# KO_V3.net
KiCad netlist of a schematic drawn in EAGLE
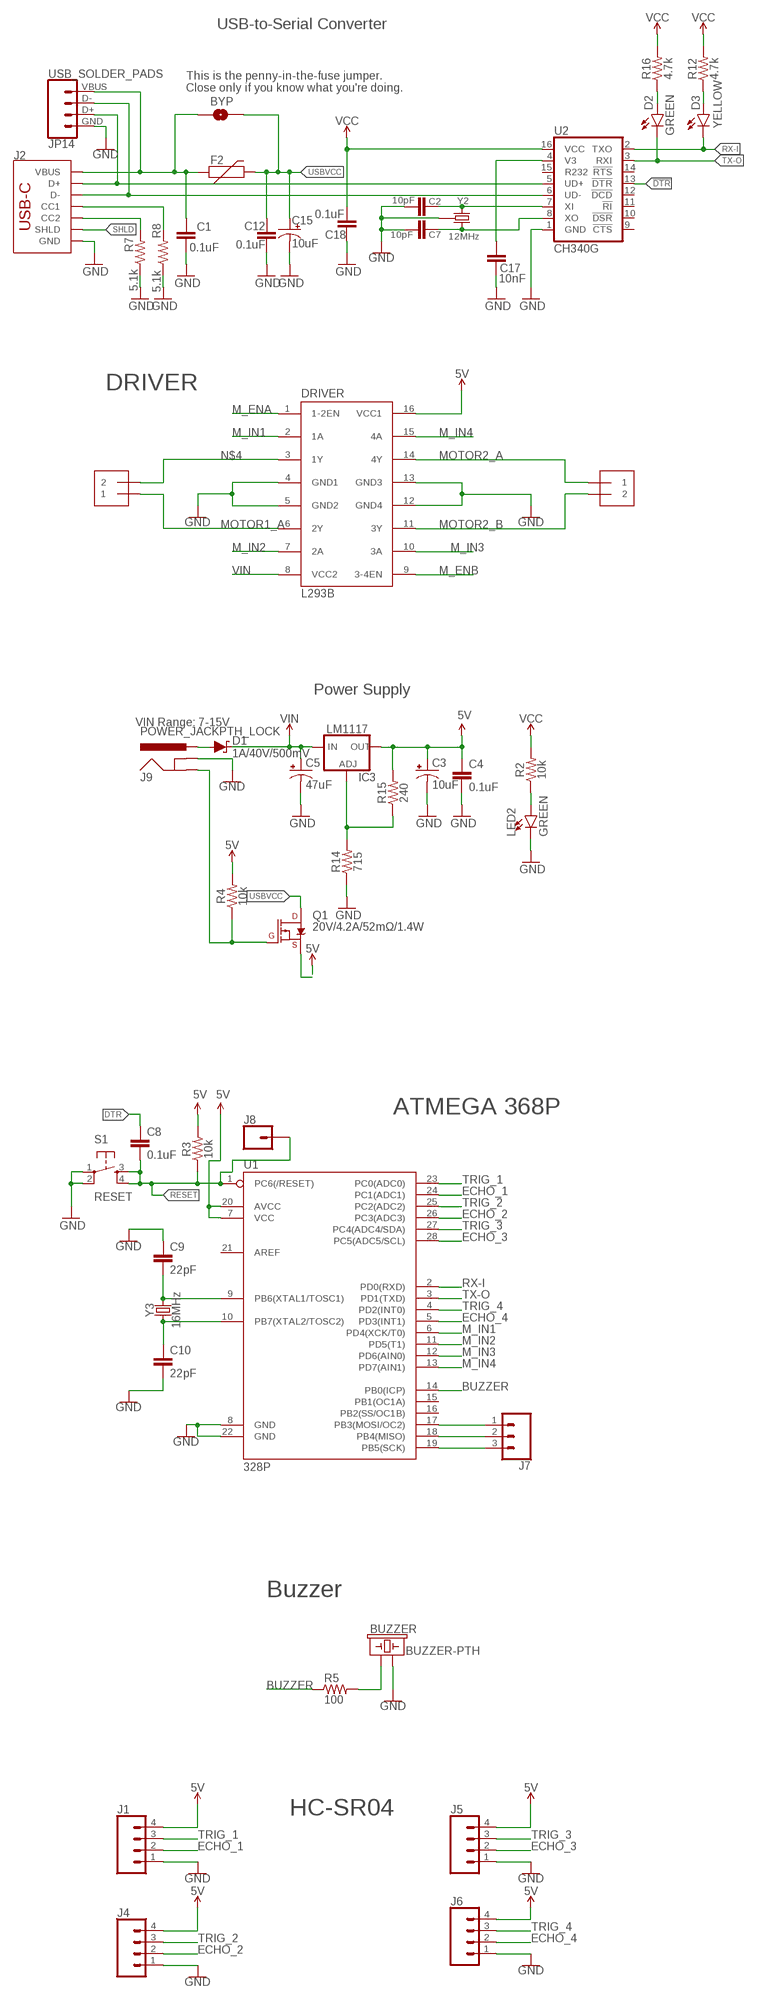
[diagram p0: schematic, sheet 1]

(export (version "E")
  (design (tool "Eeschema 10.0.6"))
  (components
    (comp (ref "BUZZER")
      (value "BUZZER-PTH")
      (footprint "eagle-import:BUZZER-12MM")
      (libsource (lib "eagle-import") (part "BUZZER-PTH"))
    )
    (comp (ref "BYP")
      (value "JUMPER-SMT_2_NO_SILK")
      (footprint "eagle-import:SMT-JUMPER_2_NO_SILK")
      (libsource (lib "eagle-import") (part "JUMPER-SMT_2_NO_SILK"))
    )
    (comp (ref "C1")
      (value "0.1uF")
      (footprint "eagle-import:0603")
      (libsource (lib "eagle-import") (part "0.1UF-0603-25V-(+80/-20%)"))
    )
    (comp (ref "C2")
      (value "10pF")
      (footprint "eagle-import:0603")
      (libsource (lib "eagle-import") (part "10PF-0603-50V-5%"))
    )
    (comp (ref "C3")
      (value "10uF")
      (footprint "eagle-import:EIA3216")
      (libsource (lib "eagle-import") (part "10UF-POLAR-EIA3216-16V-10%(TANT)"))
    )
    (comp (ref "C4")
      (value "0.1uF")
      (footprint "eagle-import:0603")
      (libsource (lib "eagle-import") (part "0.1UF-0603-25V-(+80/-20%)"))
    )
    (comp (ref "C5")
      (value "47uF")
      (footprint "eagle-import:PANASONIC_D")
      (libsource (lib "eagle-import") (part "47UF-POLAR-PANASONIC_D-35V-20%"))
    )
    (comp (ref "C7")
      (value "10pF")
      (footprint "eagle-import:0603")
      (libsource (lib "eagle-import") (part "10PF-0603-50V-5%"))
    )
    (comp (ref "C8")
      (value "0.1uF")
      (footprint "eagle-import:0603")
      (libsource (lib "eagle-import") (part "0.1UF-0603-25V-(+80/-20%)"))
    )
    (comp (ref "C9")
      (value "22pF")
      (footprint "eagle-import:0603")
      (libsource (lib "eagle-import") (part "22PF-0603-50V-5%"))
    )
    (comp (ref "C10")
      (value "22pF")
      (footprint "eagle-import:0603")
      (libsource (lib "eagle-import") (part "22PF-0603-50V-5%"))
    )
    (comp (ref "C12")
      (value "0.1uF")
      (footprint "eagle-import:0603")
      (libsource (lib "eagle-import") (part "0.1UF-0603-25V-(+80/-20%)"))
    )
    (comp (ref "C15")
      (value "10uF")
      (footprint "eagle-import:EIA3216")
      (libsource (lib "eagle-import") (part "10UF-POLAR-EIA3216-16V-10%(TANT)"))
    )
    (comp (ref "C17")
      (value "10nF")
      (footprint "eagle-import:0603")
      (libsource (lib "eagle-import") (part "10NF-0603-50V-10%"))
    )
    (comp (ref "C18")
      (value "0.1uF")
      (footprint "eagle-import:0603")
      (libsource (lib "eagle-import") (part "0.1UF-0603-25V-(+80/-20%)"))
    )
    (comp (ref "D1")
      (value "1A/40V/500mV")
      (footprint "eagle-import:SMA-DIODE")
      (libsource (lib "eagle-import") (part "DIODE-SCHOTTKY-SS14"))
    )
    (comp (ref "D2")
      (value "GREEN")
      (footprint "eagle-import:LED-1206")
      (libsource (lib "eagle-import") (part "LED-GREENLILYPAD"))
    )
    (comp (ref "D3")
      (value "YELLOW")
      (footprint "eagle-import:LED-1206-HIDDENSILK")
      (libsource (lib "eagle-import") (part "LED-YELLOW_HIDDENSILK"))
    )
    (comp (ref "DRIVER")
      (value "L293B")
      (footprint "eagle-import:DIL16")
      (fields (field (name "MPN") "L293D"))
      (libsource (lib "eagle-import") (part "L293D"))
    )
    (comp (ref "F2")
      (value "6V/2A")
      (footprint "eagle-import:1210")
      (libsource (lib "eagle-import") (part "PPTC_6V2A"))
    )
    (comp (ref "IC3")
      (value "LM1117")
      (footprint "eagle-import:SOT223")
      (fields (field (name "PROD_ID") "VREG-08170"))
      (libsource (lib "eagle-import") (part "V_REG_LM1117SOT223"))
    )
    (comp (ref "J1")
      (value "CONN_04")
      (footprint "eagle-import:1X04")
      (libsource (lib "eagle-import") (part "CONN_04"))
    )
    (comp (ref "J2")
      (value "USB Female Type C Connector")
      (footprint "eagle-import:USB-C-16P-2LAYER-PADS")
      (libsource (lib "eagle-import") (part "USB_C_2-LAYER_PADS"))
    )
    (comp (ref "J4")
      (value "CONN_04")
      (footprint "eagle-import:1X04")
      (libsource (lib "eagle-import") (part "CONN_04"))
    )
    (comp (ref "J5")
      (value "CONN_04")
      (footprint "eagle-import:1X04")
      (libsource (lib "eagle-import") (part "CONN_04"))
    )
    (comp (ref "J6")
      (value "CONN_04")
      (footprint "eagle-import:1X04")
      (libsource (lib "eagle-import") (part "CONN_04"))
    )
    (comp (ref "J7")
      (value "CONN_03LONGPADS")
      (footprint "eagle-import:1X03_LONGPADS")
      (libsource (lib "eagle-import") (part "CONN_03LONGPADS"))
    )
    (comp (ref "J8")
      (value "CONN_01OFFSET")
      (footprint "eagle-import:1X01_OFFSET")
      (libsource (lib "eagle-import") (part "CONN_01OFFSET"))
    )
    (comp (ref "J9")
      (value "POWER_JACKPTH_LOCK")
      (footprint "eagle-import:POWER_JACK_PTH_LOCK")
      (libsource (lib "eagle-import") (part "POWER_JACKPTH_LOCK"))
    )
    (comp (ref "JP14")
      (value "USB_SOLDER_PADS")
      (footprint "eagle-import:USB-SOLDER-PADS")
      (libsource (lib "eagle-import") (part "USB_SOLDER_PADS"))
    )
    (comp (ref "LED2")
      (value "GREEN")
      (footprint "eagle-import:LED-1206")
      (libsource (lib "eagle-import") (part "LED-GREENLILYPAD"))
    )
    (comp (ref "MOTOR_1")
      (value "1X2-3.5MM")
      (footprint "eagle-import:1X2-3.5MM")
      (libsource (lib "eagle-import") (part "1X2-3.5MM"))
    )
    (comp (ref "MOTOR_2")
      (value "1X2-3.5MM")
      (footprint "eagle-import:1X2-3.5MM")
      (libsource (lib "eagle-import") (part "1X2-3.5MM"))
    )
    (comp (ref "Q1")
      (value "20V/4.2A/52mΩ/1.4W")
      (footprint "eagle-import:SOT23-3")
      (libsource (lib "eagle-import") (part "MOSFET_PCH-DMG2305UX-7"))
    )
    (comp (ref "R2")
      (value "10k")
      (footprint "eagle-import:0603")
      (libsource (lib "eagle-import") (part "10KOHM-0603-1/10W-1%"))
    )
    (comp (ref "R3")
      (value "10k")
      (footprint "eagle-import:0603")
      (libsource (lib "eagle-import") (part "10KOHM-0603-1/10W-1%"))
    )
    (comp (ref "R4")
      (value "10k")
      (footprint "eagle-import:0603")
      (libsource (lib "eagle-import") (part "10KOHM-0603-1/10W-1%"))
    )
    (comp (ref "R5")
      (value "100")
      (footprint "eagle-import:RC-MASTER-SMD_R1206MP")
      (libsource (lib "eagle-import") (part "RC-MASTER-SMD_R_1206MP"))
    )
    (comp (ref "R7")
      (value "5.1k")
      (footprint "eagle-import:0603")
      (libsource (lib "eagle-import") (part "5.1KOHM5.1KOHM-0603-1/10W-1%"))
    )
    (comp (ref "R8")
      (value "5.1k")
      (footprint "eagle-import:0603")
      (libsource (lib "eagle-import") (part "5.1KOHM5.1KOHM-0603-1/10W-1%"))
    )
    (comp (ref "R12")
      (value "4.7k")
      (footprint "eagle-import:0603")
      (libsource (lib "eagle-import") (part "4.7KOHM-0603-1/10W-1%"))
    )
    (comp (ref "R14")
      (value "715")
      (footprint "eagle-import:0603")
      (libsource (lib "eagle-import") (part "715OHM-0603-1/10W-1%"))
    )
    (comp (ref "R15")
      (value "240")
      (footprint "eagle-import:0603")
      (libsource (lib "eagle-import") (part "240OHM-0603-1/10W-1%"))
    )
    (comp (ref "R16")
      (value "4.7k")
      (footprint "eagle-import:0603")
      (libsource (lib "eagle-import") (part "4.7KOHM-0603-1/10W-1%"))
    )
    (comp (ref "S1")
      (value "RESET")
      (footprint "eagle-import:TACTILE-SWITCH-SMD")
      (libsource (lib "eagle-import") (part "SWITCH_SPST_4_PINSQUARE"))
    )
    (comp (ref "U1")
      (value "328P")
      (footprint "eagle-import:DIP28")
      (libsource (lib "eagle-import") (part "ATMEGA328P_PDIP"))
    )
    (comp (ref "U2")
      (value "CH340G")
      (footprint "eagle-import:SO016")
      (libsource (lib "eagle-import") (part "CH340GSMD"))
    )
    (comp (ref "Y2")
      (value "12MHz")
      (footprint "eagle-import:CRYSTAL-SMD-3.2X2.5MM")
      (libsource (lib "eagle-import") (part "CRYSTAL-GROUNDEDSMD-3.2X2.5"))
    )
    (comp (ref "Y3")
      (value "16MHz")
      (footprint "eagle-import:HC49US")
      (libsource (lib "eagle-import") (part "CRYSTAL-16MHZPTH-HC49US"))
    )
  )
  (nets
    (net (code "1") (name "/BUZZER") (class "Default")
      (node (ref "R5") (pin "1") (pinfunction "1_1") (pintype "passive"))
      (node (ref "U1") (pin "14") (pinfunction "PB0(ICP)_14") (pintype "bidirectional"))
    )
    (net (code "2") (name "/ECHO_1") (class "Default")
      (node (ref "J1") (pin "2") (pinfunction "2_2") (pintype "passive"))
      (node (ref "U1") (pin "24") (pinfunction "PC1(ADC1)_24") (pintype "bidirectional"))
    )
    (net (code "3") (name "/ECHO_2") (class "Default")
      (node (ref "J4") (pin "2") (pinfunction "2_2") (pintype "passive"))
      (node (ref "U1") (pin "26") (pinfunction "PC3(ADC3)_26") (pintype "bidirectional"))
    )
    (net (code "4") (name "/ECHO_3") (class "Default")
      (node (ref "J5") (pin "2") (pinfunction "2_2") (pintype "passive"))
      (node (ref "U1") (pin "28") (pinfunction "PC5(ADC5/SCL)_28") (pintype "bidirectional"))
    )
    (net (code "5") (name "/ECHO_4") (class "Default")
      (node (ref "J6") (pin "2") (pinfunction "2_2") (pintype "passive"))
      (node (ref "U1") (pin "5") (pinfunction "PD3(INT1)_5") (pintype "bidirectional"))
    )
    (net (code "6") (name "/MOTOR1_A") (class "Default")
      (node (ref "DRIVER") (pin "6") (pinfunction "2Y_6") (pintype "output"))
      (node (ref "MOTOR_2") (pin "1") (pinfunction "1_1") (pintype "passive"))
    )
    (net (code "7") (name "/MOTOR2_A") (class "Default")
      (node (ref "DRIVER") (pin "14") (pinfunction "4Y_14") (pintype "output"))
      (node (ref "MOTOR_1") (pin "1") (pinfunction "1_1") (pintype "passive"))
    )
    (net (code "8") (name "/MOTOR2_B") (class "Default")
      (node (ref "DRIVER") (pin "11") (pinfunction "3Y_11") (pintype "output"))
      (node (ref "MOTOR_1") (pin "2") (pinfunction "2_2") (pintype "passive"))
    )
    (net (code "9") (name "/M_ENA") (class "Default")
      (node (ref "DRIVER") (pin "1") (pinfunction "1-2EN_1") (pintype "input"))
    )
    (net (code "10") (name "/M_ENB") (class "Default")
      (node (ref "DRIVER") (pin "9") (pinfunction "3-4EN_9") (pintype "input"))
    )
    (net (code "11") (name "/M_IN1") (class "Default")
      (node (ref "DRIVER") (pin "2") (pinfunction "1A_2") (pintype "input"))
      (node (ref "U1") (pin "6") (pinfunction "PD4(XCK/T0)_6") (pintype "bidirectional"))
    )
    (net (code "12") (name "/M_IN2") (class "Default")
      (node (ref "DRIVER") (pin "7") (pinfunction "2A_7") (pintype "input"))
      (node (ref "U1") (pin "11") (pinfunction "PD5(T1)_11") (pintype "bidirectional"))
    )
    (net (code "13") (name "/M_IN3") (class "Default")
      (node (ref "DRIVER") (pin "10") (pinfunction "3A_10") (pintype "input"))
      (node (ref "U1") (pin "12") (pinfunction "PD6(AIN0)_12") (pintype "bidirectional"))
    )
    (net (code "14") (name "/M_IN4") (class "Default")
      (node (ref "DRIVER") (pin "15") (pinfunction "4A_15") (pintype "input"))
      (node (ref "U1") (pin "13") (pinfunction "PD7(AIN1)_13") (pintype "bidirectional"))
    )
    (net (code "15") (name "/N$4") (class "Default")
      (node (ref "DRIVER") (pin "3") (pinfunction "1Y_3") (pintype "output"))
      (node (ref "MOTOR_2") (pin "2") (pinfunction "2_2") (pintype "passive"))
    )
    (net (code "16") (name "/TRIG_1") (class "Default")
      (node (ref "J1") (pin "3") (pinfunction "3_3") (pintype "passive"))
      (node (ref "U1") (pin "23") (pinfunction "PC0(ADC0)_23") (pintype "bidirectional"))
    )
    (net (code "17") (name "/TRIG_2") (class "Default")
      (node (ref "J4") (pin "3") (pinfunction "3_3") (pintype "passive"))
      (node (ref "U1") (pin "25") (pinfunction "PC2(ADC2)_25") (pintype "bidirectional"))
    )
    (net (code "18") (name "/TRIG_3") (class "Default")
      (node (ref "J5") (pin "3") (pinfunction "3_3") (pintype "passive"))
      (node (ref "U1") (pin "27") (pinfunction "PC4(ADC4/SDA)_27") (pintype "bidirectional"))
    )
    (net (code "19") (name "/TRIG_4") (class "Default")
      (node (ref "J6") (pin "3") (pinfunction "3_3") (pintype "passive"))
      (node (ref "U1") (pin "4") (pinfunction "PD2(INT0)_4") (pintype "bidirectional"))
    )
    (net (code "20") (name "/~{DTR}") (class "Default")
      (node (ref "U2") (pin "13") (pinfunction "~{DTR}_13") (pintype "bidirectional"))
    )
    (net (code "21") (name "5V") (class "Default")
      (node (ref "C3") (pin "+") (pinfunction "+_+") (pintype "passive"))
      (node (ref "C4") (pin "1") (pinfunction "1_1") (pintype "passive"))
      (node (ref "DRIVER") (pin "16") (pinfunction "VCC1_16") (pintype "power_in"))
      (node (ref "IC3") (pin "2") (pinfunction "OUT_2") (pintype "output"))
      (node (ref "IC3") (pin "4") (pinfunction "OUT_4") (pintype "output"))
      (node (ref "J1") (pin "4") (pinfunction "4_4") (pintype "passive"))
      (node (ref "J4") (pin "4") (pinfunction "4_4") (pintype "passive"))
      (node (ref "J5") (pin "4") (pinfunction "4_4") (pintype "passive"))
      (node (ref "J6") (pin "4") (pinfunction "4_4") (pintype "passive"))
      (node (ref "Q1") (pin "2") (pinfunction "S_2") (pintype "bidirectional"))
      (node (ref "R15") (pin "2") (pinfunction "2_2") (pintype "passive"))
      (node (ref "R3") (pin "2") (pinfunction "2_2") (pintype "passive"))
      (node (ref "R4") (pin "2") (pinfunction "2_2") (pintype "passive"))
      (node (ref "U1") (pin "20") (pinfunction "AVCC_20") (pintype "bidirectional"))
      (node (ref "U1") (pin "7") (pinfunction "VCC_7") (pintype "bidirectional"))
    )
    (net (code "22") (name "DTR") (class "Default")
      (node (ref "C8") (pin "1") (pinfunction "1_1") (pintype "passive"))
    )
    (net (code "23") (name "GND") (class "Default")
      (node (ref "BUZZER") (pin "-") (pinfunction "2_-") (pintype "passive"))
      (node (ref "C1") (pin "2") (pinfunction "2_2") (pintype "passive"))
      (node (ref "C10") (pin "2") (pinfunction "2_2") (pintype "passive"))
      (node (ref "C12") (pin "2") (pinfunction "2_2") (pintype "passive"))
      (node (ref "C15") (pin "-") (pinfunction "-_-") (pintype "passive"))
      (node (ref "C17") (pin "2") (pinfunction "2_2") (pintype "passive"))
      (node (ref "C18") (pin "2") (pinfunction "2_2") (pintype "passive"))
      (node (ref "C2") (pin "2") (pinfunction "2_2") (pintype "passive"))
      (node (ref "C3") (pin "-") (pinfunction "-_-") (pintype "passive"))
      (node (ref "C4") (pin "2") (pinfunction "2_2") (pintype "passive"))
      (node (ref "C5") (pin "-") (pinfunction "-_-") (pintype "passive"))
      (node (ref "C7") (pin "2") (pinfunction "2_2") (pintype "passive"))
      (node (ref "C9") (pin "1") (pinfunction "1_1") (pintype "passive"))
      (node (ref "DRIVER") (pin "12") (pinfunction "GND4_12") (pintype "power_in"))
      (node (ref "DRIVER") (pin "13") (pinfunction "GND3_13") (pintype "power_in"))
      (node (ref "DRIVER") (pin "4") (pinfunction "GND1_4") (pintype "power_in"))
      (node (ref "DRIVER") (pin "5") (pinfunction "GND2_5") (pintype "power_in"))
      (node (ref "J1") (pin "1") (pinfunction "1_1") (pintype "passive"))
      (node (ref "J2") (pin "GND") (pinfunction "GND_GND") (pintype "bidirectional"))
      (node (ref "J2") (pin "GND2") (pinfunction "GND_GND2") (pintype "bidirectional"))
      (node (ref "J4") (pin "1") (pinfunction "1_1") (pintype "passive"))
      (node (ref "J5") (pin "1") (pinfunction "1_1") (pintype "passive"))
      (node (ref "J6") (pin "1") (pinfunction "1_1") (pintype "passive"))
      (node (ref "J9") (pin "GNDBREAK") (pinfunction "GNDBREAK_GNDBREAK") (pintype "bidirectional"))
      (node (ref "JP14") (pin "GND") (pinfunction "4_GND") (pintype "passive"))
      (node (ref "LED2") (pin "C") (pinfunction "C_C") (pintype "passive"))
      (node (ref "R14") (pin "1") (pinfunction "1_1") (pintype "passive"))
      (node (ref "R7") (pin "1") (pinfunction "1_1") (pintype "passive"))
      (node (ref "R8") (pin "1") (pinfunction "1_1") (pintype "passive"))
      (node (ref "S1") (pin "1") (pinfunction "1_1") (pintype "passive"))
      (node (ref "S1") (pin "2") (pinfunction "2_2") (pintype "passive"))
      (node (ref "U1") (pin "22") (pinfunction "GND_22") (pintype "bidirectional"))
      (node (ref "U1") (pin "8") (pinfunction "GND_8") (pintype "bidirectional"))
      (node (ref "U2") (pin "1") (pinfunction "GND_1") (pintype "bidirectional"))
      (node (ref "Y2") (pin "2") (pinfunction "GND_2") (pintype "power_in"))
      (node (ref "Y2") (pin "4") (pinfunction "GND_4") (pintype "power_in"))
    )
    (net (code "24") (name "Net-(BUZZER-1)") (class "Default")
      (node (ref "BUZZER") (pin "+") (pinfunction "1_+") (pintype "passive"))
      (node (ref "R5") (pin "2") (pinfunction "2_2") (pintype "passive"))
    )
    (net (code "25") (name "Net-(D1-PadA)") (class "Default")
      (node (ref "D1") (pin "A") (pinfunction "A_A") (pintype "passive"))
      (node (ref "J9") (pin "PWR") (pinfunction "PWR_PWR") (pintype "bidirectional"))
    )
    (net (code "26") (name "Net-(D2-PadA)") (class "Default")
      (node (ref "D2") (pin "A") (pinfunction "A_A") (pintype "passive"))
      (node (ref "R16") (pin "1") (pinfunction "1_1") (pintype "passive"))
    )
    (net (code "27") (name "Net-(D3-PadA)") (class "Default")
      (node (ref "D3") (pin "A") (pinfunction "A_A") (pintype "passive"))
      (node (ref "R12") (pin "1") (pinfunction "1_1") (pintype "passive"))
    )
    (net (code "28") (name "Net-(IC3-ADJ)") (class "Default")
      (node (ref "IC3") (pin "1") (pinfunction "ADJ_1") (pintype "input"))
      (node (ref "R14") (pin "2") (pinfunction "2_2") (pintype "passive"))
      (node (ref "R15") (pin "1") (pinfunction "1_1") (pintype "passive"))
    )
    (net (code "29") (name "Net-(J2-CC1)") (class "Default")
      (node (ref "J2") (pin "A5") (pinfunction "CC1_A5") (pintype "bidirectional"))
      (node (ref "R8") (pin "2") (pinfunction "2_2") (pintype "passive"))
    )
    (net (code "30") (name "Net-(J2-CC2)") (class "Default")
      (node (ref "J2") (pin "B5") (pinfunction "CC2_B5") (pintype "bidirectional"))
      (node (ref "R7") (pin "2") (pinfunction "2_2") (pintype "passive"))
    )
    (net (code "31") (name "Net-(JP14-1)") (class "Default")
      (node (ref "BYP") (pin "1") (pinfunction "1_1") (pintype "passive"))
      (node (ref "C1") (pin "1") (pinfunction "1_1") (pintype "passive"))
      (node (ref "F2") (pin "1") (pinfunction "1_1") (pintype "bidirectional"))
      (node (ref "J2") (pin "VBUS1") (pinfunction "VBUS_VBUS1") (pintype "bidirectional"))
      (node (ref "J2") (pin "VBUS2") (pinfunction "VBUS_VBUS2") (pintype "bidirectional"))
      (node (ref "JP14") (pin "VBUS") (pinfunction "1_VBUS") (pintype "passive"))
    )
    (net (code "32") (name "Net-(JP14-2)") (class "Default")
      (node (ref "J2") (pin "A7") (pinfunction "D-_A7") (pintype "bidirectional"))
      (node (ref "J2") (pin "B7") (pinfunction "D-_B7") (pintype "bidirectional"))
      (node (ref "JP14") (pin "D-") (pinfunction "2_D-") (pintype "passive"))
      (node (ref "U2") (pin "6") (pinfunction "UD-_6") (pintype "bidirectional"))
    )
    (net (code "33") (name "Net-(JP14-3)") (class "Default")
      (node (ref "J2") (pin "A6") (pinfunction "D+_A6") (pintype "bidirectional"))
      (node (ref "J2") (pin "B6") (pinfunction "D+_B6") (pintype "bidirectional"))
      (node (ref "JP14") (pin "D+") (pinfunction "3_D+") (pintype "passive"))
      (node (ref "U2") (pin "5") (pinfunction "UD+_5") (pintype "bidirectional"))
    )
    (net (code "34") (name "Net-(LED2-PadA)") (class "Default")
      (node (ref "LED2") (pin "A") (pinfunction "A_A") (pintype "passive"))
      (node (ref "R2") (pin "1") (pinfunction "1_1") (pintype "passive"))
    )
    (net (code "35") (name "Net-(Q1-G)") (class "Default")
      (node (ref "J9") (pin "GND") (pinfunction "GND_GND") (pintype "bidirectional"))
      (node (ref "Q1") (pin "1") (pinfunction "G_1") (pintype "bidirectional"))
      (node (ref "R4") (pin "1") (pinfunction "1_1") (pintype "passive"))
    )
    (net (code "36") (name "Net-(U1-PB3(MOSI{slash}OC2))") (class "Default")
      (node (ref "J7") (pin "1") (pinfunction "1_1") (pintype "passive"))
      (node (ref "U1") (pin "17") (pinfunction "PB3(MOSI/OC2)_17") (pintype "bidirectional"))
    )
    (net (code "37") (name "Net-(U1-PB4(MISO))") (class "Default")
      (node (ref "J7") (pin "2") (pinfunction "2_2") (pintype "passive"))
      (node (ref "U1") (pin "18") (pinfunction "PB4(MISO)_18") (pintype "bidirectional"))
    )
    (net (code "38") (name "Net-(U1-PB5(SCK))") (class "Default")
      (node (ref "J7") (pin "3") (pinfunction "3_3") (pintype "passive"))
      (node (ref "U1") (pin "19") (pinfunction "PB5(SCK)_19") (pintype "bidirectional"))
    )
    (net (code "39") (name "Net-(U1-PB6(XTAL1{slash}TOSC1))") (class "Default")
      (node (ref "C9") (pin "2") (pinfunction "2_2") (pintype "passive"))
      (node (ref "U1") (pin "9") (pinfunction "PB6(XTAL1/TOSC1)_9") (pintype "bidirectional"))
      (node (ref "Y3") (pin "2") (pinfunction "2_2") (pintype "passive"))
    )
    (net (code "40") (name "Net-(U1-PB7(XTAL2{slash}TOSC2))") (class "Default")
      (node (ref "C10") (pin "1") (pinfunction "1_1") (pintype "passive"))
      (node (ref "U1") (pin "10") (pinfunction "PB7(XTAL2/TOSC2)_10") (pintype "bidirectional"))
      (node (ref "Y3") (pin "1") (pinfunction "1_1") (pintype "passive"))
    )
    (net (code "41") (name "Net-(U2-V3)") (class "Default")
      (node (ref "C17") (pin "1") (pinfunction "1_1") (pintype "passive"))
      (node (ref "U2") (pin "4") (pinfunction "V3_4") (pintype "bidirectional"))
    )
    (net (code "42") (name "Net-(U2-XI)") (class "Default")
      (node (ref "C2") (pin "1") (pinfunction "1_1") (pintype "passive"))
      (node (ref "U2") (pin "7") (pinfunction "XI_7") (pintype "bidirectional"))
      (node (ref "Y2") (pin "1") (pinfunction "1_1") (pintype "passive"))
    )
    (net (code "43") (name "Net-(U2-XO)") (class "Default")
      (node (ref "C7") (pin "1") (pinfunction "1_1") (pintype "passive"))
      (node (ref "U2") (pin "8") (pinfunction "XO_8") (pintype "bidirectional"))
      (node (ref "Y2") (pin "3") (pinfunction "2_3") (pintype "passive"))
    )
    (net (code "44") (name "RESET") (class "Default")
      (node (ref "C8") (pin "2") (pinfunction "2_2") (pintype "passive"))
      (node (ref "J8") (pin "1") (pinfunction "1_1") (pintype "passive"))
      (node (ref "R3") (pin "1") (pinfunction "1_1") (pintype "passive"))
      (node (ref "S1") (pin "3") (pinfunction "3_3") (pintype "passive"))
      (node (ref "S1") (pin "4") (pinfunction "4_4") (pintype "passive"))
      (node (ref "U1") (pin "1") (pinfunction "PC6(/RESET)_1") (pintype "bidirectional"))
    )
    (net (code "45") (name "RX-I") (class "Default")
      (node (ref "D3") (pin "C") (pinfunction "C_C") (pintype "passive"))
      (node (ref "U1") (pin "2") (pinfunction "PD0(RXD)_2") (pintype "bidirectional"))
      (node (ref "U2") (pin "2") (pinfunction "TXO_2") (pintype "bidirectional"))
    )
    (net (code "46") (name "SHLD") (class "Default")
      (node (ref "J2") (pin "SHLD1") (pinfunction "SHLD_SHLD1") (pintype "bidirectional"))
      (node (ref "J2") (pin "SHLD2") (pinfunction "SHLD_SHLD2") (pintype "bidirectional"))
      (node (ref "J2") (pin "SHLD3") (pinfunction "SHLD_SHLD3") (pintype "bidirectional"))
      (node (ref "J2") (pin "SHLD4") (pinfunction "SHLD_SHLD4") (pintype "bidirectional"))
    )
    (net (code "47") (name "TX-O") (class "Default")
      (node (ref "D2") (pin "C") (pinfunction "C_C") (pintype "passive"))
      (node (ref "U1") (pin "3") (pinfunction "PD1(TXD)_3") (pintype "bidirectional"))
      (node (ref "U2") (pin "3") (pinfunction "RXI_3") (pintype "bidirectional"))
    )
    (net (code "48") (name "USBVCC") (class "Default")
      (node (ref "BYP") (pin "2") (pinfunction "2_2") (pintype "passive"))
      (node (ref "C12") (pin "1") (pinfunction "1_1") (pintype "passive"))
      (node (ref "C15") (pin "+") (pinfunction "+_+") (pintype "passive"))
      (node (ref "F2") (pin "2") (pinfunction "2_2") (pintype "bidirectional"))
      (node (ref "Q1") (pin "3") (pinfunction "D_3") (pintype "bidirectional"))
    )
    (net (code "49") (name "VCC") (class "Default")
      (node (ref "C18") (pin "1") (pinfunction "1_1") (pintype "passive"))
      (node (ref "R12") (pin "2") (pinfunction "2_2") (pintype "passive"))
      (node (ref "R16") (pin "2") (pinfunction "2_2") (pintype "passive"))
      (node (ref "R2") (pin "2") (pinfunction "2_2") (pintype "passive"))
      (node (ref "U2") (pin "16") (pinfunction "VCC_16") (pintype "bidirectional"))
    )
    (net (code "50") (name "VIN") (class "Default")
      (node (ref "C5") (pin "+") (pinfunction "+_+") (pintype "passive"))
      (node (ref "D1") (pin "C") (pinfunction "C_C") (pintype "passive"))
      (node (ref "DRIVER") (pin "8") (pinfunction "VCC2_8") (pintype "power_in"))
      (node (ref "IC3") (pin "3") (pinfunction "IN_3") (pintype "input"))
    )
    (net (code "51") (name "unconnected-(U1-AREF-Pad21)") (class "Default")
      (node (ref "U1") (pin "21") (pinfunction "AREF_21") (pintype "bidirectional"))
    )
    (net (code "52") (name "unconnected-(U1-PB1(OC1A)-Pad15)") (class "Default")
      (node (ref "U1") (pin "15") (pinfunction "PB1(OC1A)_15") (pintype "bidirectional"))
    )
    (net (code "53") (name "unconnected-(U1-PB2(SS{slash}OC1B)-Pad16)") (class "Default")
      (node (ref "U1") (pin "16") (pinfunction "PB2(SS/OC1B)_16") (pintype "bidirectional"))
    )
    (net (code "54") (name "unconnected-(U2-R232-Pad15)") (class "Default")
      (node (ref "U2") (pin "15") (pinfunction "R232_15") (pintype "bidirectional"))
    )
    (net (code "55") (name "unconnected-(U2-~{CTS}-Pad9)") (class "Default")
      (node (ref "U2") (pin "9") (pinfunction "~{CTS}_9") (pintype "bidirectional"))
    )
    (net (code "56") (name "unconnected-(U2-~{DCD}-Pad12)") (class "Default")
      (node (ref "U2") (pin "12") (pinfunction "~{DCD}_12") (pintype "bidirectional"))
    )
    (net (code "57") (name "unconnected-(U2-~{DSR}-Pad10)") (class "Default")
      (node (ref "U2") (pin "10") (pinfunction "~{DSR}_10") (pintype "bidirectional"))
    )
    (net (code "58") (name "unconnected-(U2-~{RI}-Pad11)") (class "Default")
      (node (ref "U2") (pin "11") (pinfunction "~{RI}_11") (pintype "bidirectional"))
    )
    (net (code "59") (name "unconnected-(U2-~{RTS}-Pad14)") (class "Default")
      (node (ref "U2") (pin "14") (pinfunction "~{RTS}_14") (pintype "bidirectional"))
    )
  )
)
